# WiseClock4.net
KiCad netlist of a schematic drawn in EAGLE
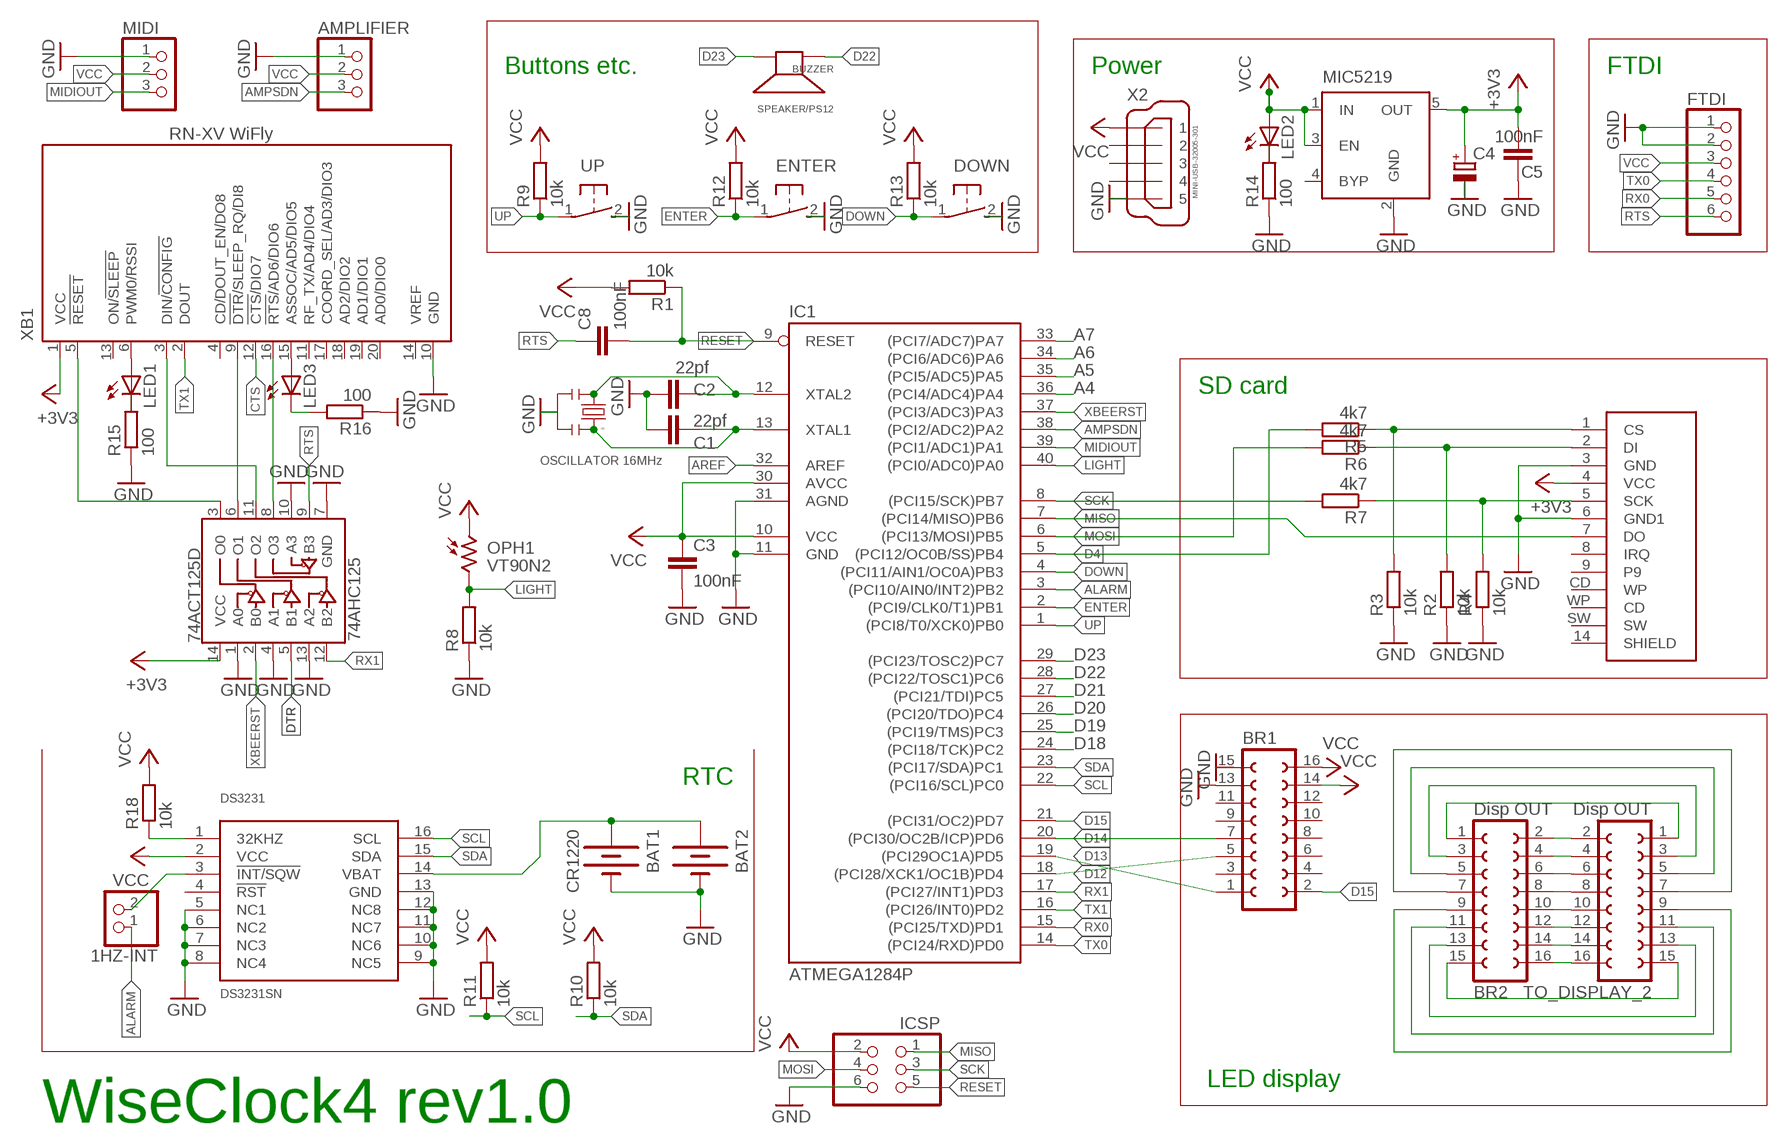
[diagram p0: schematic, sheet 1]

(export (version "E")
  (design (tool "Eeschema 10.0.6"))
  (components
    (comp (ref "1HZ-INT")
      (value "PINHD-1X2")
      (footprint "eagle-import:1X02")
      (libsource (lib "eagle-import") (part "PINHD-1X2"))
    )
    (comp (ref "74AHC125")
      (value "74ACT125D")
      (footprint "eagle-import:SO014")
      (libsource (lib "eagle-import") (part "74ACT125D"))
    )
    (comp (ref "AMPLIFIER")
      (value "PINHD-1X3")
      (footprint "eagle-import:1X03")
      (libsource (lib "eagle-import") (part "PINHD-1X3"))
    )
    (comp (ref "BAT1")
      (value "CR1220")
      (footprint "eagle-import:BAT_CR1220")
      (libsource (lib "eagle-import") (part "BATTERYBAT_CR1220"))
    )
    (comp (ref "BAT2")
      (value "BATTERY12MM")
      (footprint "eagle-import:BATTCON_12MM")
      (libsource (lib "eagle-import") (part "SparkFun6_BATTERY12MM"))
    )
    (comp (ref "BR1")
      (value "LED display")
      (footprint "eagle-import:FE08-2")
      (libsource (lib "eagle-import") (part "FE08-2"))
    )
    (comp (ref "BR2")
      (value "Disp OUT")
      (footprint "eagle-import:FE08-2")
      (libsource (lib "eagle-import") (part "FE08-2"))
    )
    (comp (ref "BUZZER")
      (value "SPEAKER/PS12")
      (footprint "eagle-import:PS12")
      (libsource (lib "eagle-import") (part "SPEAKER/PS12"))
    )
    (comp (ref "C1")
      (value "22pf")
      (footprint "eagle-import:C025-024X044")
      (libsource (lib "eagle-import") (part "C-EU025-024X044"))
    )
    (comp (ref "C2")
      (value "22pf")
      (footprint "eagle-import:C025-024X044")
      (libsource (lib "eagle-import") (part "C-EU025-024X044"))
    )
    (comp (ref "C3")
      (value "100nF")
      (footprint "eagle-import:C050-024X044")
      (libsource (lib "eagle-import") (part "C-EU050-024X044"))
    )
    (comp (ref "C4")
      (value "CPOL-EUTT2D4L")
      (footprint "eagle-import:TT2D4L")
      (libsource (lib "eagle-import") (part "CPOL-EUTT2D4L"))
    )
    (comp (ref "C5")
      (value "100nF")
      (footprint "eagle-import:C050-024X044")
      (libsource (lib "eagle-import") (part "C-EU050-024X044"))
    )
    (comp (ref "C8")
      (value "100nF")
      (footprint "eagle-import:C050-024X044")
      (libsource (lib "eagle-import") (part "C-EU050-024X044"))
    )
    (comp (ref "DOWN")
      (value "31-XX")
      (footprint "eagle-import:B3F-31XX")
      (libsource (lib "eagle-import") (part "31-XX"))
    )
    (comp (ref "DS3231")
      (value "DS3231SN")
      (footprint "eagle-import:SO16W")
      (libsource (lib "eagle-import") (part "DS3231SN"))
    )
    (comp (ref "ENTER")
      (value "31-XX")
      (footprint "eagle-import:B3F-31XX")
      (libsource (lib "eagle-import") (part "31-XX"))
    )
    (comp (ref "FTDI")
      (value "PINHD-1X6")
      (footprint "eagle-import:1X06")
      (libsource (lib "eagle-import") (part "PINHD-1X6"))
    )
    (comp (ref "IC1")
      (value "ATMEGA1284P")
      (footprint "eagle-import:DIL40")
      (libsource (lib "eagle-import") (part "ATMEGA1284P"))
    )
    (comp (ref "ICSP")
      (value "PINHD-2X3")
      (footprint "eagle-import:2X03")
      (libsource (lib "eagle-import") (part "PINHD-2X3"))
    )
    (comp (ref "LED1")
      (value "LEDCHIPLED_1206")
      (footprint "eagle-import:CHIPLED_1206")
      (libsource (lib "eagle-import") (part "LEDCHIPLED_1206"))
    )
    (comp (ref "LED2")
      (value "LEDCHIPLED_1206")
      (footprint "eagle-import:CHIPLED_1206")
      (libsource (lib "eagle-import") (part "LEDCHIPLED_1206"))
    )
    (comp (ref "LED3")
      (value "LEDCHIPLED_1206")
      (footprint "eagle-import:CHIPLED_1206")
      (libsource (lib "eagle-import") (part "LEDCHIPLED_1206"))
    )
    (comp (ref "MIC5219")
      (value "MIC5219XX")
      (footprint "eagle-import:SOT23-5")
      (libsource (lib "eagle-import") (part "MIC5219XX"))
    )
    (comp (ref "MIDI")
      (value "PINHD-1X3")
      (footprint "eagle-import:1X03")
      (libsource (lib "eagle-import") (part "PINHD-1X3"))
    )
    (comp (ref "OPH1")
      (value "VT90N2")
      (footprint "eagle-import:VT900")
      (libsource (lib "eagle-import") (part "VT90N2"))
    )
    (comp (ref "R1")
      (value "10k")
      (footprint "eagle-import:0204_7")
      (libsource (lib "eagle-import") (part "R-EU_0204/7"))
    )
    (comp (ref "R2")
      (value "10k")
      (footprint "eagle-import:0204_7")
      (libsource (lib "eagle-import") (part "R-EU_0204/7"))
    )
    (comp (ref "R3")
      (value "10k")
      (footprint "eagle-import:0204_7")
      (libsource (lib "eagle-import") (part "R-EU_0204/7"))
    )
    (comp (ref "R4")
      (value "10k")
      (footprint "eagle-import:0204_7")
      (libsource (lib "eagle-import") (part "R-EU_0204/7"))
    )
    (comp (ref "R5")
      (value "4k7")
      (footprint "eagle-import:0204_7")
      (libsource (lib "eagle-import") (part "R-EU_0204/7"))
    )
    (comp (ref "R6")
      (value "4k7")
      (footprint "eagle-import:0204_7")
      (libsource (lib "eagle-import") (part "R-EU_0204/7"))
    )
    (comp (ref "R7")
      (value "4k7")
      (footprint "eagle-import:0204_7")
      (libsource (lib "eagle-import") (part "R-EU_0204/7"))
    )
    (comp (ref "R8")
      (value "10k")
      (footprint "eagle-import:0204_7")
      (libsource (lib "eagle-import") (part "R-EU_0204/7"))
    )
    (comp (ref "R9")
      (value "10k")
      (footprint "eagle-import:0204_7")
      (libsource (lib "eagle-import") (part "R-EU_0204/7"))
    )
    (comp (ref "R10")
      (value "10k")
      (footprint "eagle-import:0204_7")
      (libsource (lib "eagle-import") (part "R-EU_0204/7"))
    )
    (comp (ref "R11")
      (value "10k")
      (footprint "eagle-import:0204_7")
      (libsource (lib "eagle-import") (part "R-EU_0204/7"))
    )
    (comp (ref "R12")
      (value "10k")
      (footprint "eagle-import:0204_7")
      (libsource (lib "eagle-import") (part "R-EU_0204/7"))
    )
    (comp (ref "R13")
      (value "10k")
      (footprint "eagle-import:0204_7")
      (libsource (lib "eagle-import") (part "R-EU_0204/7"))
    )
    (comp (ref "R14")
      (value "100")
      (footprint "eagle-import:M0805")
      (libsource (lib "eagle-import") (part "R-EU_M0805"))
    )
    (comp (ref "R15")
      (value "100")
      (footprint "eagle-import:M0805")
      (libsource (lib "eagle-import") (part "R-EU_M0805"))
    )
    (comp (ref "R16")
      (value "100")
      (footprint "eagle-import:M0805")
      (libsource (lib "eagle-import") (part "R-EU_M0805"))
    )
    (comp (ref "R18")
      (value "10k")
      (footprint "eagle-import:0204_7")
      (libsource (lib "eagle-import") (part "R-EU_0204/7"))
    )
    (comp (ref "SDCARD")
      (value "SD_CARD_SOCKETSD")
      (footprint "eagle-import:SD-MMC_SOCKET-PP")
      (libsource (lib "eagle-import") (part "SD_CARD_SOCKETSD"))
    )
    (comp (ref "TO_DISPLAY_2")
      (value "Disp OUT")
      (footprint "eagle-import:FE08-2")
      (libsource (lib "eagle-import") (part "FE08-2"))
    )
    (comp (ref "U$1")
      (value "OSCILLATOR 16MHz")
      (footprint "eagle-import:RESONATOR-PTH")
      (libsource (lib "eagle-import") (part "RESONATORPTH"))
    )
    (comp (ref "UP")
      (value "31-XX")
      (footprint "eagle-import:B3F-31XX")
      (libsource (lib "eagle-import") (part "31-XX"))
    )
    (comp (ref "X2")
      (value "MINI-USB-32005-301")
      (footprint "eagle-import:32005-301")
      (libsource (lib "eagle-import") (part "MINI-USB-32005-301"))
    )
    (comp (ref "XB1")
      (value "RN-XV WiFly")
      (footprint "eagle-import:XBEE-PRO")
      (libsource (lib "eagle-import") (part "XBEE-PRO"))
    )
  )
  (nets
    (net (code "1") (name "+3V3") (class "Default")
      (node (ref "74AHC125") (pin "14") (pinfunction "VCC_14") (pintype "bidirectional"))
      (node (ref "C4") (pin "+") (pinfunction "+_+") (pintype "passive"))
      (node (ref "C5") (pin "2") (pinfunction "2_2") (pintype "passive"))
      (node (ref "MIC5219") (pin "5") (pinfunction "OUT_5") (pintype "output"))
      (node (ref "SDCARD") (pin "4") (pinfunction "VCC_4") (pintype "bidirectional"))
      (node (ref "XB1") (pin "1") (pinfunction "VCC_1") (pintype "power_in"))
    )
    (net (code "2") (name "/A4") (class "Default")
      (node (ref "IC1") (pin "36") (pinfunction "(PCI4/ADC4)PA4_36") (pintype "bidirectional"))
    )
    (net (code "3") (name "/A5") (class "Default")
      (node (ref "IC1") (pin "35") (pinfunction "(PCI5/ADC5)PA5_35") (pintype "bidirectional"))
    )
    (net (code "4") (name "/A6") (class "Default")
      (node (ref "IC1") (pin "34") (pinfunction "(PCI6/ADC6)PA6_34") (pintype "bidirectional"))
    )
    (net (code "5") (name "/A7") (class "Default")
      (node (ref "IC1") (pin "33") (pinfunction "(PCI7/ADC7)PA7_33") (pintype "bidirectional"))
    )
    (net (code "6") (name "/D18") (class "Default")
      (node (ref "IC1") (pin "24") (pinfunction "(PCI18/TCK)PC2_24") (pintype "bidirectional"))
    )
    (net (code "7") (name "/D19") (class "Default")
      (node (ref "IC1") (pin "25") (pinfunction "(PCI19/TMS)PC3_25") (pintype "bidirectional"))
    )
    (net (code "8") (name "/D20") (class "Default")
      (node (ref "IC1") (pin "26") (pinfunction "(PCI20/TDO)PC4_26") (pintype "bidirectional"))
    )
    (net (code "9") (name "/D21") (class "Default")
      (node (ref "IC1") (pin "27") (pinfunction "(PCI21/TDI)PC5_27") (pintype "bidirectional"))
    )
    (net (code "10") (name "ALARM") (class "Default")
      (node (ref "1HZ-INT") (pin "1") (pinfunction "1_1") (pintype "passive"))
      (node (ref "IC1") (pin "3") (pinfunction "(PCI10/AIN0/INT2)PB2_3") (pintype "bidirectional"))
    )
    (net (code "11") (name "AMPSDN") (class "Default")
      (node (ref "AMPLIFIER") (pin "3") (pinfunction "3_3") (pintype "passive"))
      (node (ref "IC1") (pin "38") (pinfunction "(PCI2/ADC2)PA2_38") (pintype "bidirectional"))
    )
    (net (code "12") (name "AREF") (class "Default")
      (node (ref "IC1") (pin "32") (pinfunction "AREF_32") (pintype "power_in"))
    )
    (net (code "13") (name "CTS") (class "Default")
      (node (ref "XB1") (pin "12") (pinfunction "~{CTS}/DIO7_12") (pintype "bidirectional"))
    )
    (net (code "14") (name "D4") (class "Default")
      (node (ref "IC1") (pin "5") (pinfunction "(PCI12/OC0B/SS)PB4_5") (pintype "bidirectional"))
      (node (ref "R5") (pin "2") (pinfunction "2_2") (pintype "passive"))
    )
    (net (code "15") (name "D12") (class "Default")
      (node (ref "BR1") (pin "5") (pinfunction "5_5") (pintype "passive"))
      (node (ref "IC1") (pin "18") (pinfunction "(PCI28/XCK1/OC1B)PD4_18") (pintype "bidirectional"))
    )
    (net (code "16") (name "D13") (class "Default")
      (node (ref "BR1") (pin "1") (pinfunction "1_1") (pintype "passive"))
      (node (ref "IC1") (pin "19") (pinfunction "(PCI29OC1A)PD5_19") (pintype "bidirectional"))
    )
    (net (code "17") (name "D14") (class "Default")
      (node (ref "BR1") (pin "7") (pinfunction "7_7") (pintype "passive"))
      (node (ref "IC1") (pin "20") (pinfunction "(PCI30/OC2B/ICP)PD6_20") (pintype "bidirectional"))
    )
    (net (code "18") (name "D15") (class "Default")
      (node (ref "BR1") (pin "2") (pinfunction "2_2") (pintype "passive"))
      (node (ref "IC1") (pin "21") (pinfunction "(PCI31/OC2)PD7_21") (pintype "bidirectional"))
    )
    (net (code "19") (name "D22") (class "Default")
      (node (ref "BUZZER") (pin "P$1") (pinfunction "+_P$1") (pintype "passive"))
      (node (ref "IC1") (pin "28") (pinfunction "(PCI22/TOSC1)PC6_28") (pintype "bidirectional"))
    )
    (net (code "20") (name "D23") (class "Default")
      (node (ref "BUZZER") (pin "P$2") (pinfunction "-_P$2") (pintype "passive"))
      (node (ref "IC1") (pin "29") (pinfunction "(PCI23/TOSC2)PC7_29") (pintype "bidirectional"))
    )
    (net (code "21") (name "DOWN") (class "Default")
      (node (ref "DOWN") (pin "1") (pinfunction "P_1") (pintype "passive"))
      (node (ref "IC1") (pin "4") (pinfunction "(PCI11/AIN1/OC0A)PB3_4") (pintype "bidirectional"))
      (node (ref "R13") (pin "1") (pinfunction "1_1") (pintype "passive"))
    )
    (net (code "22") (name "DTR") (class "Default")
      (node (ref "74AHC125") (pin "5") (pinfunction "B1_5") (pintype "bidirectional"))
    )
    (net (code "23") (name "ENTER") (class "Default")
      (node (ref "ENTER") (pin "1") (pinfunction "P_1") (pintype "passive"))
      (node (ref "IC1") (pin "2") (pinfunction "(PCI9/CLK0/T1)PB1_2") (pintype "bidirectional"))
      (node (ref "R12") (pin "1") (pinfunction "1_1") (pintype "passive"))
    )
    (net (code "24") (name "GND") (class "Default")
      (node (ref "74AHC125") (pin "1") (pinfunction "A0_1") (pintype "bidirectional"))
      (node (ref "74AHC125") (pin "10") (pinfunction "A3_10") (pintype "bidirectional"))
      (node (ref "74AHC125") (pin "13") (pinfunction "A2_13") (pintype "bidirectional"))
      (node (ref "74AHC125") (pin "4") (pinfunction "A1_4") (pintype "bidirectional"))
      (node (ref "74AHC125") (pin "7") (pinfunction "GND_7") (pintype "bidirectional"))
      (node (ref "AMPLIFIER") (pin "1") (pinfunction "1_1") (pintype "passive"))
      (node (ref "BAT1") (pin "GND") (pinfunction "-_GND") (pintype "power_in"))
      (node (ref "BAT2") (pin "GND") (pinfunction "-_GND") (pintype "power_in"))
      (node (ref "BR1") (pin "13") (pinfunction "13_13") (pintype "passive"))
      (node (ref "BR1") (pin "15") (pinfunction "15_15") (pintype "passive"))
      (node (ref "C1") (pin "1") (pinfunction "1_1") (pintype "passive"))
      (node (ref "C2") (pin "1") (pinfunction "1_1") (pintype "passive"))
      (node (ref "C3") (pin "2") (pinfunction "2_2") (pintype "passive"))
      (node (ref "C4") (pin "-") (pinfunction "-_-") (pintype "passive"))
      (node (ref "C5") (pin "1") (pinfunction "1_1") (pintype "passive"))
      (node (ref "DOWN") (pin "2") (pinfunction "S_2") (pintype "passive"))
      (node (ref "DS3231") (pin "10") (pinfunction "NC6_10") (pintype "bidirectional"))
      (node (ref "DS3231") (pin "11") (pinfunction "NC7_11") (pintype "bidirectional"))
      (node (ref "DS3231") (pin "12") (pinfunction "NC8_12") (pintype "bidirectional"))
      (node (ref "DS3231") (pin "13") (pinfunction "GND_13") (pintype "bidirectional"))
      (node (ref "DS3231") (pin "5") (pinfunction "NC1_5") (pintype "bidirectional"))
      (node (ref "DS3231") (pin "6") (pinfunction "NC2_6") (pintype "bidirectional"))
      (node (ref "DS3231") (pin "7") (pinfunction "NC3_7") (pintype "bidirectional"))
      (node (ref "DS3231") (pin "8") (pinfunction "NC4_8") (pintype "bidirectional"))
      (node (ref "DS3231") (pin "9") (pinfunction "NC5_9") (pintype "bidirectional"))
      (node (ref "ENTER") (pin "2") (pinfunction "S_2") (pintype "passive"))
      (node (ref "FTDI") (pin "1") (pinfunction "1_1") (pintype "passive"))
      (node (ref "FTDI") (pin "2") (pinfunction "2_2") (pintype "passive"))
      (node (ref "IC1") (pin "11") (pinfunction "GND_11") (pintype "power_in"))
      (node (ref "IC1") (pin "31") (pinfunction "AGND_31") (pintype "power_in"))
      (node (ref "ICSP") (pin "6") (pinfunction "6_6") (pintype "passive"))
      (node (ref "MIC5219") (pin "2") (pinfunction "GND_2") (pintype "power_in"))
      (node (ref "MIDI") (pin "1") (pinfunction "1_1") (pintype "passive"))
      (node (ref "R14") (pin "1") (pinfunction "1_1") (pintype "passive"))
      (node (ref "R15") (pin "1") (pinfunction "1_1") (pintype "passive"))
      (node (ref "R16") (pin "1") (pinfunction "1_1") (pintype "passive"))
      (node (ref "R2") (pin "1") (pinfunction "1_1") (pintype "passive"))
      (node (ref "R3") (pin "1") (pinfunction "1_1") (pintype "passive"))
      (node (ref "R4") (pin "1") (pinfunction "1_1") (pintype "passive"))
      (node (ref "R8") (pin "1") (pinfunction "1_1") (pintype "passive"))
      (node (ref "SDCARD") (pin "3") (pinfunction "GND_3") (pintype "bidirectional"))
      (node (ref "SDCARD") (pin "6") (pinfunction "GND1_6") (pintype "bidirectional"))
      (node (ref "U$1") (pin "2") (pinfunction "2_2") (pintype "passive"))
      (node (ref "UP") (pin "2") (pinfunction "S_2") (pintype "passive"))
      (node (ref "X2") (pin "5") (pinfunction "5_5") (pintype "passive"))
      (node (ref "XB1") (pin "10") (pinfunction "GND_10") (pintype "power_in"))
    )
    (net (code "25") (name "LIGHT") (class "Default")
      (node (ref "IC1") (pin "40") (pinfunction "(PCI0/ADC0)PA0_40") (pintype "bidirectional"))
      (node (ref "OPH1") (pin "2") (pinfunction "2_2") (pintype "passive"))
      (node (ref "R8") (pin "2") (pinfunction "2_2") (pintype "passive"))
    )
    (net (code "26") (name "MIDIOUT") (class "Default")
      (node (ref "IC1") (pin "39") (pinfunction "(PCI1/ADC1)PA1_39") (pintype "bidirectional"))
      (node (ref "MIDI") (pin "3") (pinfunction "3_3") (pintype "passive"))
    )
    (net (code "27") (name "MISO") (class "Default")
      (node (ref "IC1") (pin "7") (pinfunction "(PCI14/MISO)PB6_7") (pintype "bidirectional"))
      (node (ref "ICSP") (pin "1") (pinfunction "1_1") (pintype "passive"))
      (node (ref "SDCARD") (pin "7") (pinfunction "DO_7") (pintype "bidirectional"))
    )
    (net (code "28") (name "MOSI") (class "Default")
      (node (ref "IC1") (pin "6") (pinfunction "(PCI13/MOSI)PB5_6") (pintype "bidirectional"))
      (node (ref "ICSP") (pin "4") (pinfunction "4_4") (pintype "passive"))
      (node (ref "R6") (pin "2") (pinfunction "2_2") (pintype "passive"))
    )
    (net (code "29") (name "Net-(74AHC125-O0)") (class "Default")
      (node (ref "74AHC125") (pin "3") (pinfunction "O0_3") (pintype "bidirectional"))
      (node (ref "XB1") (pin "5") (pinfunction "~{RESET}_5") (pintype "input"))
    )
    (net (code "30") (name "Net-(74AHC125-O1)") (class "Default")
      (node (ref "74AHC125") (pin "6") (pinfunction "O1_6") (pintype "bidirectional"))
      (node (ref "XB1") (pin "9") (pinfunction "~{DTR}/SLEEP_RQ/DI8_9") (pintype "bidirectional"))
    )
    (net (code "31") (name "Net-(74AHC125-O2)") (class "Default")
      (node (ref "74AHC125") (pin "11") (pinfunction "O2_11") (pintype "bidirectional"))
      (node (ref "XB1") (pin "3") (pinfunction "DIN/~{CONFIG}_3") (pintype "input"))
    )
    (net (code "32") (name "Net-(74AHC125-O3)") (class "Default")
      (node (ref "74AHC125") (pin "8") (pinfunction "O3_8") (pintype "bidirectional"))
      (node (ref "XB1") (pin "16") (pinfunction "~{RTS}/AD6/DIO6_16") (pintype "bidirectional"))
    )
    (net (code "33") (name "Net-(BAT1-+)") (class "Default")
      (node (ref "BAT1") (pin "V+") (pinfunction "+_V+") (pintype "power_in"))
      (node (ref "BAT2") (pin "PWR@1") (pinfunction "+_PWR@1") (pintype "power_in"))
      (node (ref "DS3231") (pin "14") (pinfunction "VBAT_14") (pintype "bidirectional"))
    )
    (net (code "34") (name "Net-(BR2-Pad1)") (class "Default")
      (node (ref "BR2") (pin "1") (pinfunction "1_1") (pintype "passive"))
      (node (ref "TO_DISPLAY_2") (pin "1") (pinfunction "1_1") (pintype "passive"))
    )
    (net (code "35") (name "Net-(BR2-Pad2)") (class "Default")
      (node (ref "BR2") (pin "2") (pinfunction "2_2") (pintype "passive"))
      (node (ref "TO_DISPLAY_2") (pin "2") (pinfunction "2_2") (pintype "passive"))
    )
    (net (code "36") (name "Net-(BR2-Pad3)") (class "Default")
      (node (ref "BR2") (pin "3") (pinfunction "3_3") (pintype "passive"))
      (node (ref "TO_DISPLAY_2") (pin "3") (pinfunction "3_3") (pintype "passive"))
    )
    (net (code "37") (name "Net-(BR2-Pad4)") (class "Default")
      (node (ref "BR2") (pin "4") (pinfunction "4_4") (pintype "passive"))
      (node (ref "TO_DISPLAY_2") (pin "4") (pinfunction "4_4") (pintype "passive"))
    )
    (net (code "38") (name "Net-(BR2-Pad5)") (class "Default")
      (node (ref "BR2") (pin "5") (pinfunction "5_5") (pintype "passive"))
      (node (ref "TO_DISPLAY_2") (pin "5") (pinfunction "5_5") (pintype "passive"))
    )
    (net (code "39") (name "Net-(BR2-Pad6)") (class "Default")
      (node (ref "BR2") (pin "6") (pinfunction "6_6") (pintype "passive"))
      (node (ref "TO_DISPLAY_2") (pin "6") (pinfunction "6_6") (pintype "passive"))
    )
    (net (code "40") (name "Net-(BR2-Pad7)") (class "Default")
      (node (ref "BR2") (pin "7") (pinfunction "7_7") (pintype "passive"))
      (node (ref "TO_DISPLAY_2") (pin "7") (pinfunction "7_7") (pintype "passive"))
    )
    (net (code "41") (name "Net-(BR2-Pad8)") (class "Default")
      (node (ref "BR2") (pin "8") (pinfunction "8_8") (pintype "passive"))
      (node (ref "TO_DISPLAY_2") (pin "8") (pinfunction "8_8") (pintype "passive"))
    )
    (net (code "42") (name "Net-(BR2-Pad9)") (class "Default")
      (node (ref "BR2") (pin "9") (pinfunction "9_9") (pintype "passive"))
      (node (ref "TO_DISPLAY_2") (pin "9") (pinfunction "9_9") (pintype "passive"))
    )
    (net (code "43") (name "Net-(BR2-Pad10)") (class "Default")
      (node (ref "BR2") (pin "10") (pinfunction "10_10") (pintype "passive"))
      (node (ref "TO_DISPLAY_2") (pin "10") (pinfunction "10_10") (pintype "passive"))
    )
    (net (code "44") (name "Net-(BR2-Pad11)") (class "Default")
      (node (ref "BR2") (pin "11") (pinfunction "11_11") (pintype "passive"))
      (node (ref "TO_DISPLAY_2") (pin "11") (pinfunction "11_11") (pintype "passive"))
    )
    (net (code "45") (name "Net-(BR2-Pad12)") (class "Default")
      (node (ref "BR2") (pin "12") (pinfunction "12_12") (pintype "passive"))
      (node (ref "TO_DISPLAY_2") (pin "12") (pinfunction "12_12") (pintype "passive"))
    )
    (net (code "46") (name "Net-(BR2-Pad13)") (class "Default")
      (node (ref "BR2") (pin "13") (pinfunction "13_13") (pintype "passive"))
      (node (ref "TO_DISPLAY_2") (pin "13") (pinfunction "13_13") (pintype "passive"))
    )
    (net (code "47") (name "Net-(BR2-Pad14)") (class "Default")
      (node (ref "BR2") (pin "14") (pinfunction "14_14") (pintype "passive"))
      (node (ref "TO_DISPLAY_2") (pin "14") (pinfunction "14_14") (pintype "passive"))
    )
    (net (code "48") (name "Net-(BR2-Pad15)") (class "Default")
      (node (ref "BR2") (pin "15") (pinfunction "15_15") (pintype "passive"))
      (node (ref "TO_DISPLAY_2") (pin "15") (pinfunction "15_15") (pintype "passive"))
    )
    (net (code "49") (name "Net-(BR2-Pad16)") (class "Default")
      (node (ref "BR2") (pin "16") (pinfunction "16_16") (pintype "passive"))
      (node (ref "TO_DISPLAY_2") (pin "16") (pinfunction "16_16") (pintype "passive"))
    )
    (net (code "50") (name "Net-(DS3231-32KHZ)") (class "Default")
      (node (ref "DS3231") (pin "1") (pinfunction "32KHZ_1") (pintype "bidirectional"))
      (node (ref "R18") (pin "1") (pinfunction "1_1") (pintype "passive"))
    )
    (net (code "51") (name "Net-(DS3231-~{INT{slash}SQW})") (class "Default")
      (node (ref "1HZ-INT") (pin "2") (pinfunction "2_2") (pintype "passive"))
      (node (ref "DS3231") (pin "3") (pinfunction "~{INT/SQW}_3") (pintype "bidirectional"))
    )
    (net (code "52") (name "Net-(IC1-XTAL1)") (class "Default")
      (node (ref "C1") (pin "2") (pinfunction "2_2") (pintype "passive"))
      (node (ref "IC1") (pin "13") (pinfunction "XTAL1_13") (pintype "bidirectional"))
      (node (ref "U$1") (pin "3") (pinfunction "3_3") (pintype "passive"))
    )
    (net (code "53") (name "Net-(IC1-XTAL2)") (class "Default")
      (node (ref "C2") (pin "2") (pinfunction "2_2") (pintype "passive"))
      (node (ref "IC1") (pin "12") (pinfunction "XTAL2_12") (pintype "bidirectional"))
      (node (ref "U$1") (pin "1") (pinfunction "1_1") (pintype "passive"))
    )
    (net (code "54") (name "Net-(LED1-PadC)") (class "Default")
      (node (ref "LED1") (pin "C") (pinfunction "C_C") (pintype "passive"))
      (node (ref "R15") (pin "2") (pinfunction "2_2") (pintype "passive"))
    )
    (net (code "55") (name "Net-(LED2-PadC)") (class "Default")
      (node (ref "LED2") (pin "C") (pinfunction "C_C") (pintype "passive"))
      (node (ref "R14") (pin "2") (pinfunction "2_2") (pintype "passive"))
    )
    (net (code "56") (name "Net-(LED3-PadC)") (class "Default")
      (node (ref "LED3") (pin "C") (pinfunction "C_C") (pintype "passive"))
      (node (ref "R16") (pin "2") (pinfunction "2_2") (pintype "passive"))
    )
    (net (code "57") (name "Net-(SDCARD-CS)") (class "Default")
      (node (ref "R3") (pin "2") (pinfunction "2_2") (pintype "passive"))
      (node (ref "R5") (pin "1") (pinfunction "1_1") (pintype "passive"))
      (node (ref "SDCARD") (pin "1") (pinfunction "CS_1") (pintype "bidirectional"))
    )
    (net (code "58") (name "Net-(SDCARD-DI)") (class "Default")
      (node (ref "R2") (pin "2") (pinfunction "2_2") (pintype "passive"))
      (node (ref "R6") (pin "1") (pinfunction "1_1") (pintype "passive"))
      (node (ref "SDCARD") (pin "2") (pinfunction "DI_2") (pintype "bidirectional"))
    )
    (net (code "59") (name "Net-(SDCARD-SCK)") (class "Default")
      (node (ref "R4") (pin "2") (pinfunction "2_2") (pintype "passive"))
      (node (ref "R7") (pin "1") (pinfunction "1_1") (pintype "passive"))
      (node (ref "SDCARD") (pin "5") (pinfunction "SCK_5") (pintype "bidirectional"))
    )
    (net (code "60") (name "Net-(XB1-ASSOC{slash}AD5{slash}DIO5)") (class "Default")
      (node (ref "LED3") (pin "A") (pinfunction "A_A") (pintype "passive"))
      (node (ref "XB1") (pin "15") (pinfunction "ASSOC/AD5/DIO5_15") (pintype "bidirectional"))
    )
    (net (code "61") (name "Net-(XB1-PWM0{slash}RSSI)") (class "Default")
      (node (ref "LED1") (pin "A") (pinfunction "A_A") (pintype "passive"))
      (node (ref "XB1") (pin "6") (pinfunction "PWM0/RSSI_6") (pintype "output"))
    )
    (net (code "62") (name "RESET") (class "Default")
      (node (ref "C8") (pin "2") (pinfunction "2_2") (pintype "passive"))
      (node (ref "IC1") (pin "9") (pinfunction "RESET_9") (pintype "input"))
      (node (ref "ICSP") (pin "5") (pinfunction "5_5") (pintype "passive"))
      (node (ref "R1") (pin "1") (pinfunction "1_1") (pintype "passive"))
    )
    (net (code "63") (name "RTS") (class "Default")
      (node (ref "74AHC125") (pin "9") (pinfunction "B3_9") (pintype "bidirectional"))
      (node (ref "C8") (pin "1") (pinfunction "1_1") (pintype "passive"))
      (node (ref "FTDI") (pin "6") (pinfunction "6_6") (pintype "passive"))
    )
    (net (code "64") (name "RX0") (class "Default")
      (node (ref "FTDI") (pin "5") (pinfunction "5_5") (pintype "passive"))
      (node (ref "IC1") (pin "15") (pinfunction "(PCI25/TXD)PD1_15") (pintype "bidirectional"))
    )
    (net (code "65") (name "RX1") (class "Default")
      (node (ref "74AHC125") (pin "12") (pinfunction "B2_12") (pintype "bidirectional"))
      (node (ref "IC1") (pin "17") (pinfunction "(PCI27/INT1)PD3_17") (pintype "bidirectional"))
    )
    (net (code "66") (name "SCK") (class "Default")
      (node (ref "IC1") (pin "8") (pinfunction "(PCI15/SCK)PB7_8") (pintype "bidirectional"))
      (node (ref "ICSP") (pin "3") (pinfunction "3_3") (pintype "passive"))
      (node (ref "R7") (pin "2") (pinfunction "2_2") (pintype "passive"))
    )
    (net (code "67") (name "SCL") (class "Default")
      (node (ref "DS3231") (pin "16") (pinfunction "SCL_16") (pintype "bidirectional"))
      (node (ref "IC1") (pin "22") (pinfunction "(PCI16/SCL)PC0_22") (pintype "bidirectional"))
      (node (ref "R11") (pin "1") (pinfunction "1_1") (pintype "passive"))
    )
    (net (code "68") (name "SDA") (class "Default")
      (node (ref "DS3231") (pin "15") (pinfunction "SDA_15") (pintype "bidirectional"))
      (node (ref "IC1") (pin "23") (pinfunction "(PCI17/SDA)PC1_23") (pintype "bidirectional"))
      (node (ref "R10") (pin "1") (pinfunction "1_1") (pintype "passive"))
    )
    (net (code "69") (name "TX0") (class "Default")
      (node (ref "FTDI") (pin "4") (pinfunction "4_4") (pintype "passive"))
      (node (ref "IC1") (pin "14") (pinfunction "(PCI24/RXD)PD0_14") (pintype "bidirectional"))
    )
    (net (code "70") (name "TX1") (class "Default")
      (node (ref "IC1") (pin "16") (pinfunction "(PCI26/INT0)PD2_16") (pintype "bidirectional"))
      (node (ref "XB1") (pin "2") (pinfunction "DOUT_2") (pintype "output"))
    )
    (net (code "71") (name "UP") (class "Default")
      (node (ref "IC1") (pin "1") (pinfunction "(PCI8/T0/XCK0)PB0_1") (pintype "bidirectional"))
      (node (ref "R9") (pin "1") (pinfunction "1_1") (pintype "passive"))
      (node (ref "UP") (pin "1") (pinfunction "P_1") (pintype "passive"))
    )
    (net (code "72") (name "VCC") (class "Default")
      (node (ref "AMPLIFIER") (pin "2") (pinfunction "2_2") (pintype "passive"))
      (node (ref "BR1") (pin "14") (pinfunction "14_14") (pintype "passive"))
      (node (ref "BR1") (pin "16") (pinfunction "16_16") (pintype "passive"))
      (node (ref "C3") (pin "1") (pinfunction "1_1") (pintype "passive"))
      (node (ref "DS3231") (pin "2") (pinfunction "VCC_2") (pintype "bidirectional"))
      (node (ref "FTDI") (pin "3") (pinfunction "3_3") (pintype "passive"))
      (node (ref "IC1") (pin "10") (pinfunction "VCC_10") (pintype "power_in"))
      (node (ref "IC1") (pin "30") (pinfunction "AVCC_30") (pintype "power_in"))
      (node (ref "ICSP") (pin "2") (pinfunction "2_2") (pintype "passive"))
      (node (ref "LED2") (pin "A") (pinfunction "A_A") (pintype "passive"))
      (node (ref "MIC5219") (pin "1") (pinfunction "IN_1") (pintype "input"))
      (node (ref "MIC5219") (pin "3") (pinfunction "EN_3") (pintype "input"))
      (node (ref "MIDI") (pin "2") (pinfunction "2_2") (pintype "passive"))
      (node (ref "OPH1") (pin "1") (pinfunction "1_1") (pintype "passive"))
      (node (ref "R1") (pin "2") (pinfunction "2_2") (pintype "passive"))
      (node (ref "R10") (pin "2") (pinfunction "2_2") (pintype "passive"))
      (node (ref "R11") (pin "2") (pinfunction "2_2") (pintype "passive"))
      (node (ref "R12") (pin "2") (pinfunction "2_2") (pintype "passive"))
      (node (ref "R13") (pin "2") (pinfunction "2_2") (pintype "passive"))
      (node (ref "R18") (pin "2") (pinfunction "2_2") (pintype "passive"))
      (node (ref "R9") (pin "2") (pinfunction "2_2") (pintype "passive"))
      (node (ref "X2") (pin "1") (pinfunction "1_1") (pintype "passive"))
    )
    (net (code "73") (name "XBEERST") (class "Default")
      (node (ref "74AHC125") (pin "2") (pinfunction "B0_2") (pintype "bidirectional"))
      (node (ref "IC1") (pin "37") (pinfunction "(PCI3/ADC3)PA3_37") (pintype "bidirectional"))
    )
    (net (code "74") (name "unconnected-(BR1-Pad3)") (class "Default")
      (node (ref "BR1") (pin "3") (pinfunction "3_3") (pintype "passive"))
    )
    (net (code "75") (name "unconnected-(BR1-Pad4)") (class "Default")
      (node (ref "BR1") (pin "4") (pinfunction "4_4") (pintype "passive"))
    )
    (net (code "76") (name "unconnected-(BR1-Pad6)") (class "Default")
      (node (ref "BR1") (pin "6") (pinfunction "6_6") (pintype "passive"))
    )
    (net (code "77") (name "unconnected-(BR1-Pad8)") (class "Default")
      (node (ref "BR1") (pin "8") (pinfunction "8_8") (pintype "passive"))
    )
    (net (code "78") (name "unconnected-(BR1-Pad9)") (class "Default")
      (node (ref "BR1") (pin "9") (pinfunction "9_9") (pintype "passive"))
    )
    (net (code "79") (name "unconnected-(BR1-Pad10)") (class "Default")
      (node (ref "BR1") (pin "10") (pinfunction "10_10") (pintype "passive"))
    )
    (net (code "80") (name "unconnected-(BR1-Pad11)") (class "Default")
      (node (ref "BR1") (pin "11") (pinfunction "11_11") (pintype "passive"))
    )
    (net (code "81") (name "unconnected-(BR1-Pad12)") (class "Default")
      (node (ref "BR1") (pin "12") (pinfunction "12_12") (pintype "passive"))
    )
    (net (code "82") (name "unconnected-(DS3231-~{RST}-Pad4)") (class "Default")
      (node (ref "DS3231") (pin "4") (pinfunction "~{RST}_4") (pintype "bidirectional"))
    )
    (net (code "83") (name "unconnected-(MIC5219-BYP-Pad4)") (class "Default")
      (node (ref "MIC5219") (pin "4") (pinfunction "BYP_4") (pintype "passive"))
    )
    (net (code "84") (name "unconnected-(SDCARD-CD-PadWP)") (class "Default")
      (node (ref "SDCARD") (pin "WP") (pinfunction "CD_WP") (pintype "bidirectional"))
    )
    (net (code "85") (name "unconnected-(SDCARD-IRQ-Pad8)") (class "Default")
      (node (ref "SDCARD") (pin "8") (pinfunction "IRQ_8") (pintype "bidirectional"))
    )
    (net (code "86") (name "unconnected-(SDCARD-P9-Pad9)") (class "Default")
      (node (ref "SDCARD") (pin "9") (pinfunction "P9_9") (pintype "bidirectional"))
    )
    (net (code "87") (name "unconnected-(SDCARD-PadSW)") (class "Default")
      (node (ref "SDCARD") (pin "SW") (pinfunction "SW_SW") (pintype "bidirectional"))
    )
    (net (code "88") (name "unconnected-(SDCARD-SHIELD-Pad14)") (class "Default")
      (node (ref "SDCARD") (pin "14") (pinfunction "SHIELD_14") (pintype "bidirectional"))
    )
    (net (code "89") (name "unconnected-(SDCARD-WP-PadCD)") (class "Default")
      (node (ref "SDCARD") (pin "CD") (pinfunction "WP_CD") (pintype "bidirectional"))
    )
    (net (code "90") (name "unconnected-(X2-Pad2)") (class "Default")
      (node (ref "X2") (pin "2") (pinfunction "2_2") (pintype "passive"))
    )
    (net (code "91") (name "unconnected-(X2-Pad3)") (class "Default")
      (node (ref "X2") (pin "3") (pinfunction "3_3") (pintype "passive"))
    )
    (net (code "92") (name "unconnected-(X2-Pad4)") (class "Default")
      (node (ref "X2") (pin "4") (pinfunction "4_4") (pintype "passive"))
    )
    (net (code "93") (name "unconnected-(XB1-AD0{slash}DIO0-Pad20)") (class "Default")
      (node (ref "XB1") (pin "20") (pinfunction "AD0/DIO0_20") (pintype "bidirectional"))
    )
    (net (code "94") (name "unconnected-(XB1-AD1{slash}DIO1-Pad19)") (class "Default")
      (node (ref "XB1") (pin "19") (pinfunction "AD1/DIO1_19") (pintype "bidirectional"))
    )
    (net (code "95") (name "unconnected-(XB1-AD2{slash}DIO2-Pad18)") (class "Default")
      (node (ref "XB1") (pin "18") (pinfunction "AD2/DIO2_18") (pintype "bidirectional"))
    )
    (net (code "96") (name "unconnected-(XB1-CD{slash}DOUT_EN{slash}DO8-Pad4)") (class "Default")
      (node (ref "XB1") (pin "4") (pinfunction "CD/DOUT_EN/DO8_4") (pintype "output"))
    )
    (net (code "97") (name "unconnected-(XB1-COORD_SEL{slash}AD3{slash}DIO3-Pad17)") (class "Default")
      (node (ref "XB1") (pin "17") (pinfunction "COORD_SEL/AD3/DIO3_17") (pintype "bidirectional"))
    )
    (net (code "98") (name "unconnected-(XB1-ON{slash}~{SLEEP}-Pad13)") (class "Default")
      (node (ref "XB1") (pin "13") (pinfunction "ON/~{SLEEP}_13") (pintype "output"))
    )
    (net (code "99") (name "unconnected-(XB1-RF_TX{slash}AD4{slash}DIO4-Pad11)") (class "Default")
      (node (ref "XB1") (pin "11") (pinfunction "RF_TX/AD4/DIO4_11") (pintype "bidirectional"))
    )
    (net (code "100") (name "unconnected-(XB1-VREF-Pad14)") (class "Default")
      (node (ref "XB1") (pin "14") (pinfunction "VREF_14") (pintype "input"))
    )
  )
)
